# SCH_555LEDCHASER1_2025-11-26.net
KiCad netlist of a schematic drawn in EasyEDA
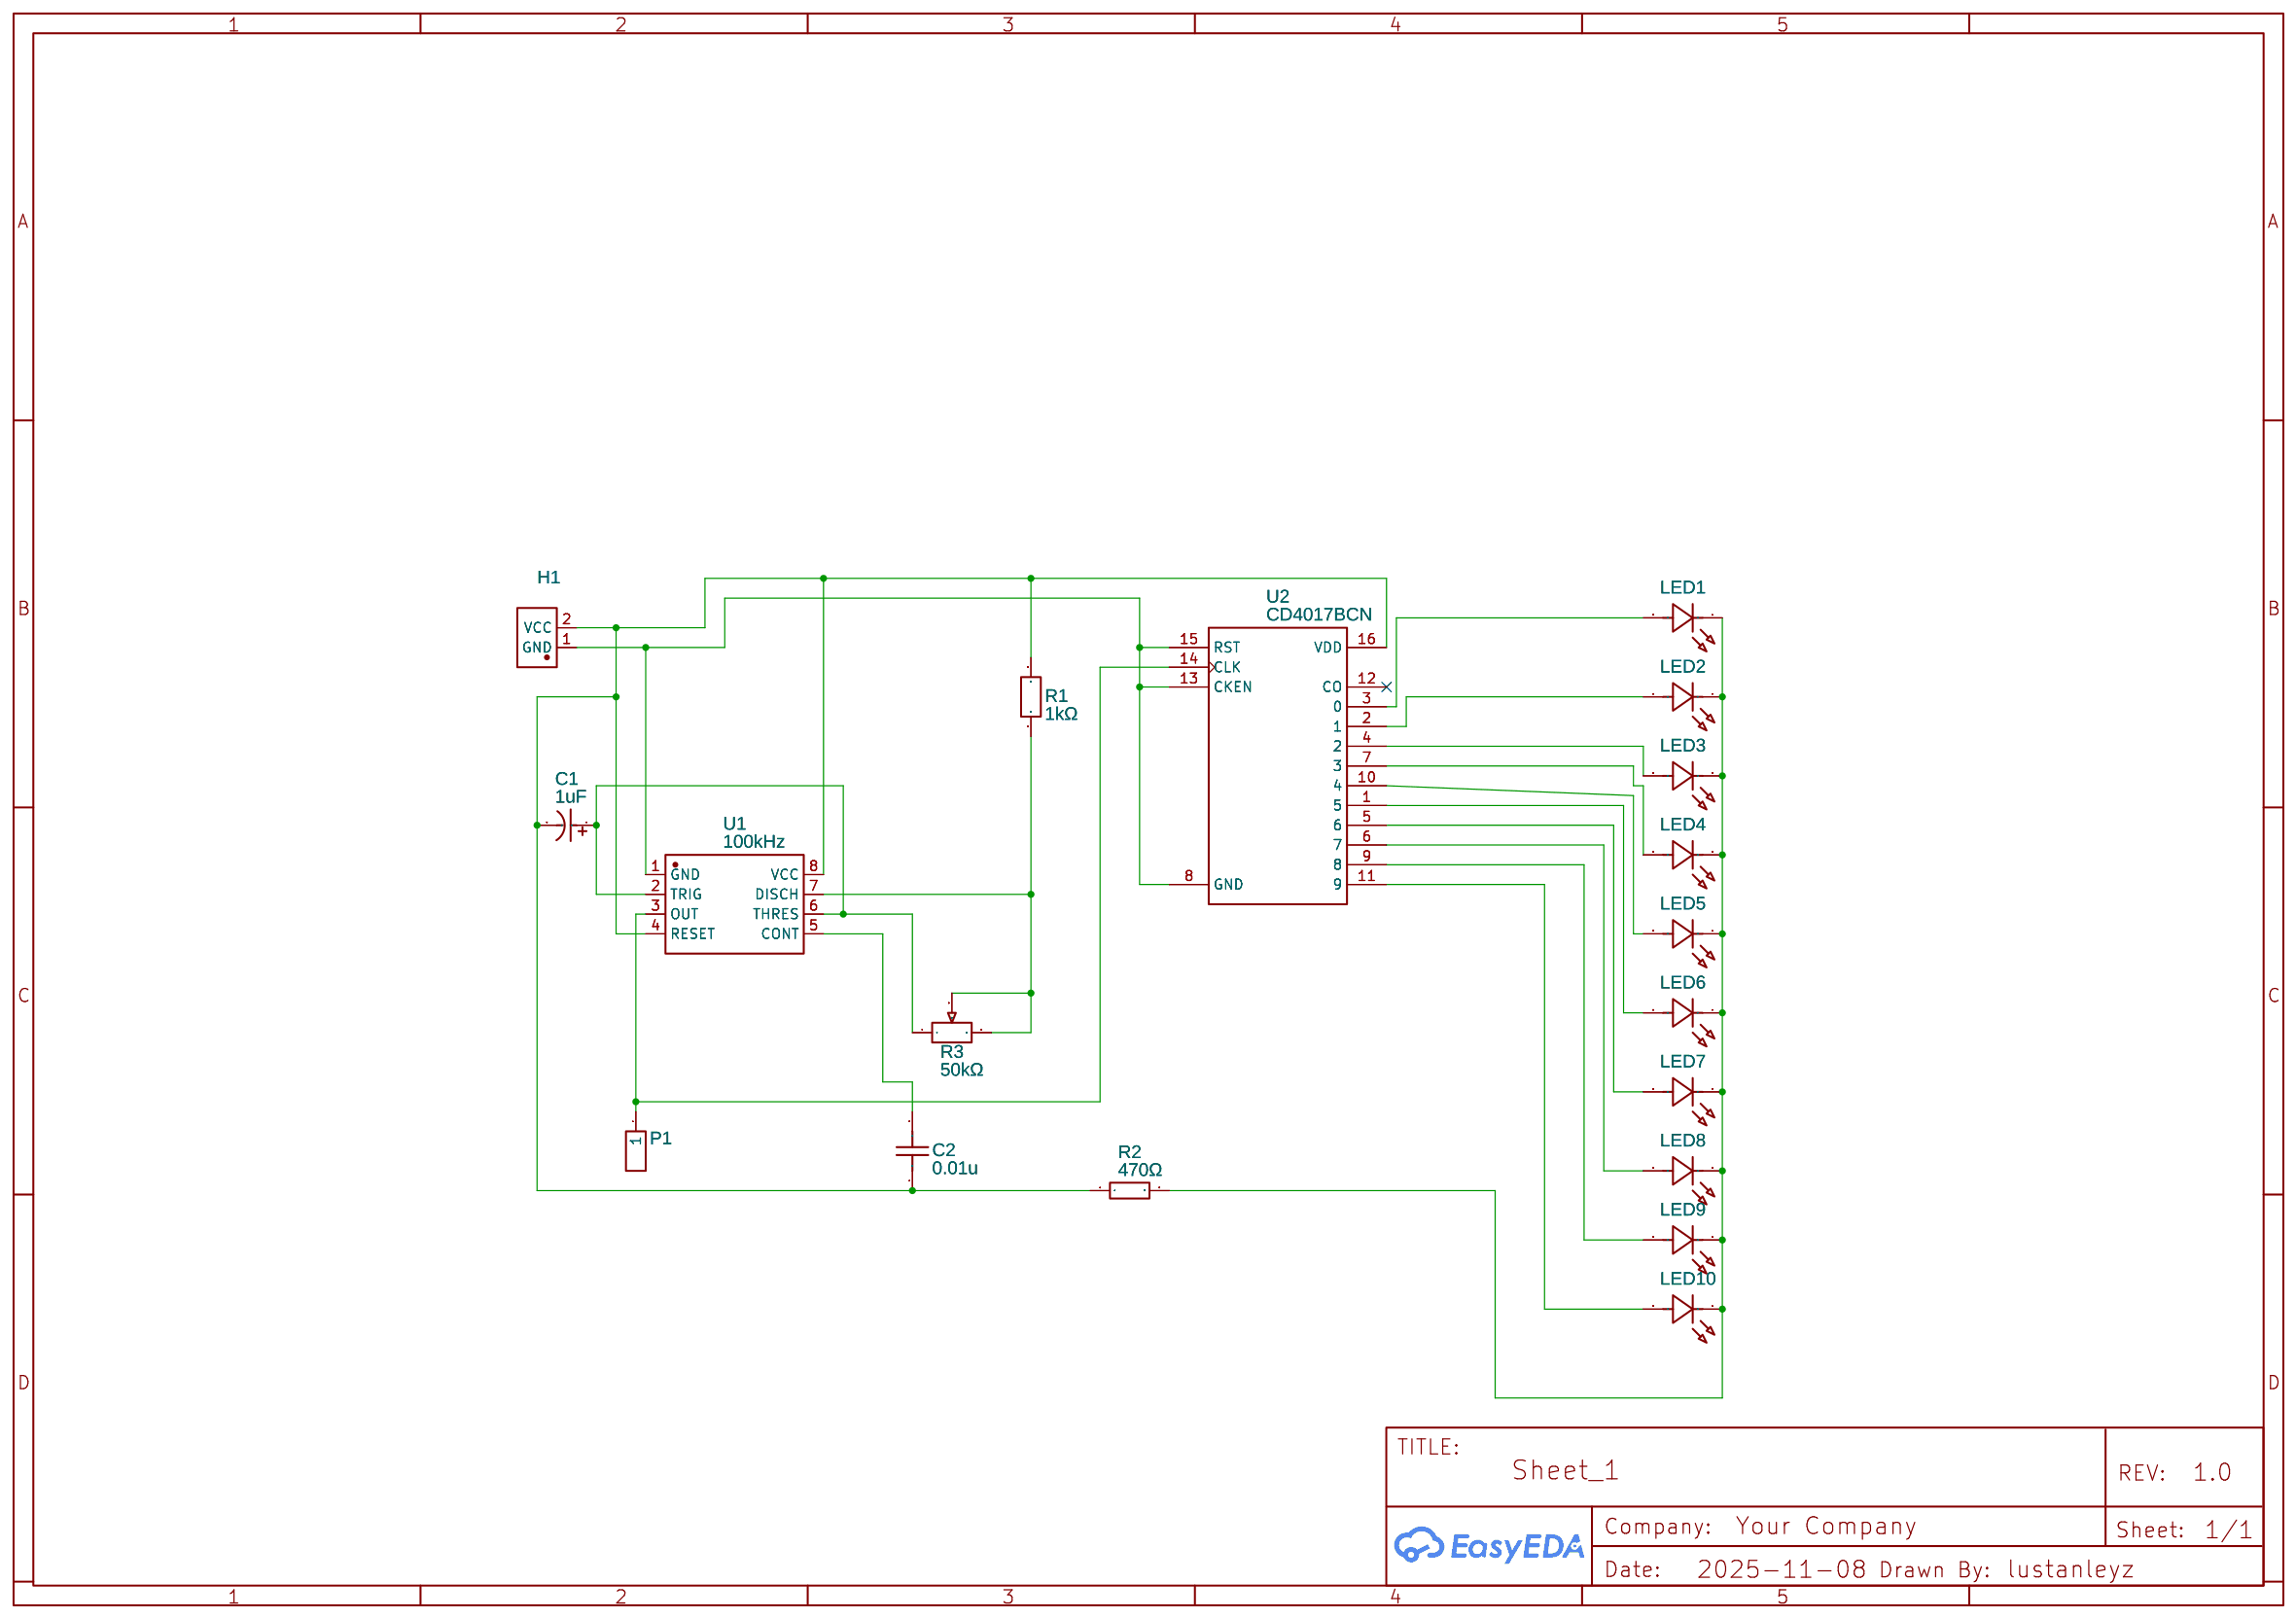
[diagram p0: schematic sheet]

(export (version "E")
  (design (tool "Eeschema 10.0.6"))
  (components
    (comp (ref "C1")
      (value "1uF")
      (fields (field (name "Manufacturer Part") "KF010M050C110A") (field (name "Manufacturer") "CapXon(丰宾)"))
      (libsource (lib "") (part "KF010M050C110A"))
    )
    (comp (ref "C2")
      (value "0.01u")
      (fields (field (name "Manufacturer Part") "N09F1B103MN0B0S0N0") (field (name "Manufacturer") "STE(松田)"))
      (libsource (lib "") (part "N09F1B103MN0B0S0N0"))
    )
    (comp (ref "H1")
      (value "PZ254V-11-02P")
      (fields (field (name "Manufacturer") "XFCN(兴飞)"))
      (libsource (lib "") (part "PZ254V-11-02P"))
    )
    (comp (ref "LED1")
      (value "XL-502UWC")
      (fields (field (name "Manufacturer") "XINGLIGHT(成兴光)"))
      (libsource (lib "") (part "XL-502UWC"))
    )
    (comp (ref "LED2")
      (value "XL-502UWC")
      (fields (field (name "Manufacturer") "XINGLIGHT(成兴光)"))
      (libsource (lib "") (part "XL-502UWC"))
    )
    (comp (ref "LED3")
      (value "XL-502UWC")
      (fields (field (name "Manufacturer") "XINGLIGHT(成兴光)"))
      (libsource (lib "") (part "XL-502UWC"))
    )
    (comp (ref "LED4")
      (value "XL-502UWC")
      (fields (field (name "Manufacturer") "XINGLIGHT(成兴光)"))
      (libsource (lib "") (part "XL-502UWC"))
    )
    (comp (ref "LED5")
      (value "XL-502UWC")
      (fields (field (name "Manufacturer") "XINGLIGHT(成兴光)"))
      (libsource (lib "") (part "XL-502UWC"))
    )
    (comp (ref "LED6")
      (value "XL-502UWC")
      (fields (field (name "Manufacturer") "XINGLIGHT(成兴光)"))
      (libsource (lib "") (part "XL-502UWC"))
    )
    (comp (ref "LED7")
      (value "XL-502UWC")
      (fields (field (name "Manufacturer") "XINGLIGHT(成兴光)"))
      (libsource (lib "") (part "XL-502UWC"))
    )
    (comp (ref "LED8")
      (value "XL-502UWC")
      (fields (field (name "Manufacturer") "XINGLIGHT(成兴光)"))
      (libsource (lib "") (part "XL-502UWC"))
    )
    (comp (ref "LED9")
      (value "XL-502UWC")
      (fields (field (name "Manufacturer") "XINGLIGHT(成兴光)"))
      (libsource (lib "") (part "XL-502UWC"))
    )
    (comp (ref "LED10")
      (value "XL-502UWC")
      (fields (field (name "Manufacturer") "XINGLIGHT(成兴光)"))
      (libsource (lib "") (part "XL-502UWC"))
    )
    (comp (ref "P1")
      (value "Header-Male-2.54_1x1")
      (fields (field (name "Manufacturer Part") "2.54-1*1P针") (field (name "Manufacturer") "BOOMELE(博穆精密)"))
      (libsource (lib "") (part "Header-Male-2.54_1x1"))
    )
    (comp (ref "R1")
      (value "1kΩ")
      (fields (field (name "Manufacturer Part") "MF1/4W-1KΩ±1%T52") (field (name "Manufacturer") "华星机电"))
      (libsource (lib "") (part "MF1/4W-1KΩ±1%T52"))
    )
    (comp (ref "R2")
      (value "470Ω")
      (fields
        (field (name "Manufacturer Part") "MFR0W4F4700A50")
        (field (name "Manufacturer") "UNI-ROYAL(厚声)")
      )
      (libsource (lib "") (part "MFR0W4F4700A50"))
    )
    (comp (ref "R3")
      (value "50kΩ")
      (fields (field (name "Manufacturer Part") "3296X-1-503") (field (name "Manufacturer") "BOCHEN(博晨)"))
      (libsource (lib "") (part "3296X-1-503_C118912"))
    )
    (comp (ref "U1")
      (value "100kHz")
      (fields (field (name "Manufacturer Part") "NE555P") (field (name "Manufacturer") "TI(德州仪器)"))
      (libsource (lib "") (part "NE555P"))
    )
    (comp (ref "U2") (value "CD4017BCN") (libsource (lib "") (part "CD4017BCN")))
  )
  (nets
    (net (code "1") (name "Net-(H1-GND)") (class "Default")
      (node (ref "H1") (pin "1") (pinfunction "GND_1") (pintype "unspecified"))
      (node (ref "U1") (pin "1") (pinfunction "GND_1") (pintype "unspecified"))
      (node (ref "U2") (pin "13") (pinfunction "CKEN_13") (pintype "unspecified"))
      (node (ref "U2") (pin "15") (pinfunction "RST_15") (pintype "unspecified"))
      (node (ref "U2") (pin "8") (pinfunction "GND_8") (pintype "passive"))
    )
    (net (code "2") (name "Net-(H1-VCC)") (class "Default")
      (node (ref "C1") (pin "2") (pinfunction "2_2") (pintype "input"))
      (node (ref "C2") (pin "1") (pinfunction "1_1") (pintype "unspecified"))
      (node (ref "H1") (pin "2") (pinfunction "VCC_2") (pintype "unspecified"))
      (node (ref "R1") (pin "2") (pinfunction "2_2") (pintype "unspecified"))
      (node (ref "R2") (pin "1") (pinfunction "1_1") (pintype "input"))
      (node (ref "U1") (pin "4") (pinfunction "RESET_4") (pintype "unspecified"))
      (node (ref "U1") (pin "8") (pinfunction "VCC_8") (pintype "unspecified"))
      (node (ref "U2") (pin "16") (pinfunction "VDD_16") (pintype "passive"))
    )
    (net (code "3") (name "Net-(LED1-A)") (class "Default")
      (node (ref "LED1") (pin "2") (pinfunction "A_2") (pintype "unspecified"))
      (node (ref "U2") (pin "3") (pinfunction "0_3") (pintype "output"))
    )
    (net (code "4") (name "Net-(LED1-K)") (class "Default")
      (node (ref "LED1") (pin "1") (pinfunction "K_1") (pintype "unspecified"))
      (node (ref "LED10") (pin "1") (pinfunction "K_1") (pintype "unspecified"))
      (node (ref "LED2") (pin "1") (pinfunction "K_1") (pintype "unspecified"))
      (node (ref "LED3") (pin "1") (pinfunction "K_1") (pintype "unspecified"))
      (node (ref "LED4") (pin "1") (pinfunction "K_1") (pintype "unspecified"))
      (node (ref "LED5") (pin "1") (pinfunction "K_1") (pintype "unspecified"))
      (node (ref "LED6") (pin "1") (pinfunction "K_1") (pintype "unspecified"))
      (node (ref "LED7") (pin "1") (pinfunction "K_1") (pintype "unspecified"))
      (node (ref "LED8") (pin "1") (pinfunction "K_1") (pintype "unspecified"))
      (node (ref "LED9") (pin "1") (pinfunction "K_1") (pintype "unspecified"))
      (node (ref "R2") (pin "2") (pinfunction "2_2") (pintype "input"))
    )
    (net (code "5") (name "Net-(LED2-A)") (class "Default")
      (node (ref "LED2") (pin "2") (pinfunction "A_2") (pintype "unspecified"))
      (node (ref "U2") (pin "2") (pinfunction "1_2") (pintype "output"))
    )
    (net (code "6") (name "Net-(LED3-A)") (class "Default")
      (node (ref "LED3") (pin "2") (pinfunction "A_2") (pintype "unspecified"))
      (node (ref "U2") (pin "4") (pinfunction "2_4") (pintype "output"))
    )
    (net (code "7") (name "Net-(LED4-A)") (class "Default")
      (node (ref "LED4") (pin "2") (pinfunction "A_2") (pintype "unspecified"))
      (node (ref "U2") (pin "7") (pinfunction "3_7") (pintype "output"))
    )
    (net (code "8") (name "Net-(LED5-A)") (class "Default")
      (node (ref "LED5") (pin "2") (pinfunction "A_2") (pintype "unspecified"))
      (node (ref "U2") (pin "10") (pinfunction "4_10") (pintype "output"))
    )
    (net (code "9") (name "Net-(LED6-A)") (class "Default")
      (node (ref "LED6") (pin "2") (pinfunction "A_2") (pintype "unspecified"))
      (node (ref "U2") (pin "1") (pinfunction "5_1") (pintype "output"))
    )
    (net (code "10") (name "Net-(LED7-A)") (class "Default")
      (node (ref "LED7") (pin "2") (pinfunction "A_2") (pintype "unspecified"))
      (node (ref "U2") (pin "5") (pinfunction "6_5") (pintype "output"))
    )
    (net (code "11") (name "Net-(LED8-A)") (class "Default")
      (node (ref "LED8") (pin "2") (pinfunction "A_2") (pintype "unspecified"))
      (node (ref "U2") (pin "6") (pinfunction "7_6") (pintype "output"))
    )
    (net (code "12") (name "Net-(LED9-A)") (class "Default")
      (node (ref "LED9") (pin "2") (pinfunction "A_2") (pintype "unspecified"))
      (node (ref "U2") (pin "9") (pinfunction "8_9") (pintype "output"))
    )
    (net (code "13") (name "Net-(LED10-A)") (class "Default")
      (node (ref "LED10") (pin "2") (pinfunction "A_2") (pintype "unspecified"))
      (node (ref "U2") (pin "11") (pinfunction "9_11") (pintype "output"))
    )
    (net (code "14") (name "Net-(U1-CONT)") (class "Default")
      (node (ref "C2") (pin "2") (pinfunction "2_2") (pintype "unspecified"))
      (node (ref "U1") (pin "5") (pinfunction "CONT_5") (pintype "unspecified"))
    )
    (net (code "15") (name "Net-(U1-DISCH)") (class "Default")
      (node (ref "R1") (pin "1") (pinfunction "1_1") (pintype "unspecified"))
      (node (ref "R3") (pin "2") (pinfunction "2_2") (pintype "input"))
      (node (ref "R3") (pin "3") (pinfunction "3_3") (pintype "input"))
      (node (ref "U1") (pin "7") (pinfunction "DISCH_7") (pintype "unspecified"))
    )
    (net (code "16") (name "Net-(U1-OUT)") (class "Default")
      (node (ref "P1") (pin "1") (pinfunction "1_1") (pintype "input"))
      (node (ref "U1") (pin "3") (pinfunction "OUT_3") (pintype "unspecified"))
      (node (ref "U2") (pin "14") (pinfunction "CLK_14") (pintype "unspecified"))
    )
    (net (code "17") (name "Net-(U1-THRES)") (class "Default")
      (node (ref "C1") (pin "1") (pinfunction "1_1") (pintype "input"))
      (node (ref "R3") (pin "1") (pinfunction "1_1") (pintype "input"))
      (node (ref "U1") (pin "2") (pinfunction "TRIG_2") (pintype "unspecified"))
      (node (ref "U1") (pin "6") (pinfunction "THRES_6") (pintype "unspecified"))
    )
    (net (code "18") (name "unconnected-(U2-CO-Pad12)") (class "Default")
      (node (ref "U2") (pin "12") (pinfunction "CO_12") (pintype "output+no_connect"))
    )
  )
)
